# Macro_Mini_keypad.net
KiCad netlist of a schematic drawn in EAGLE
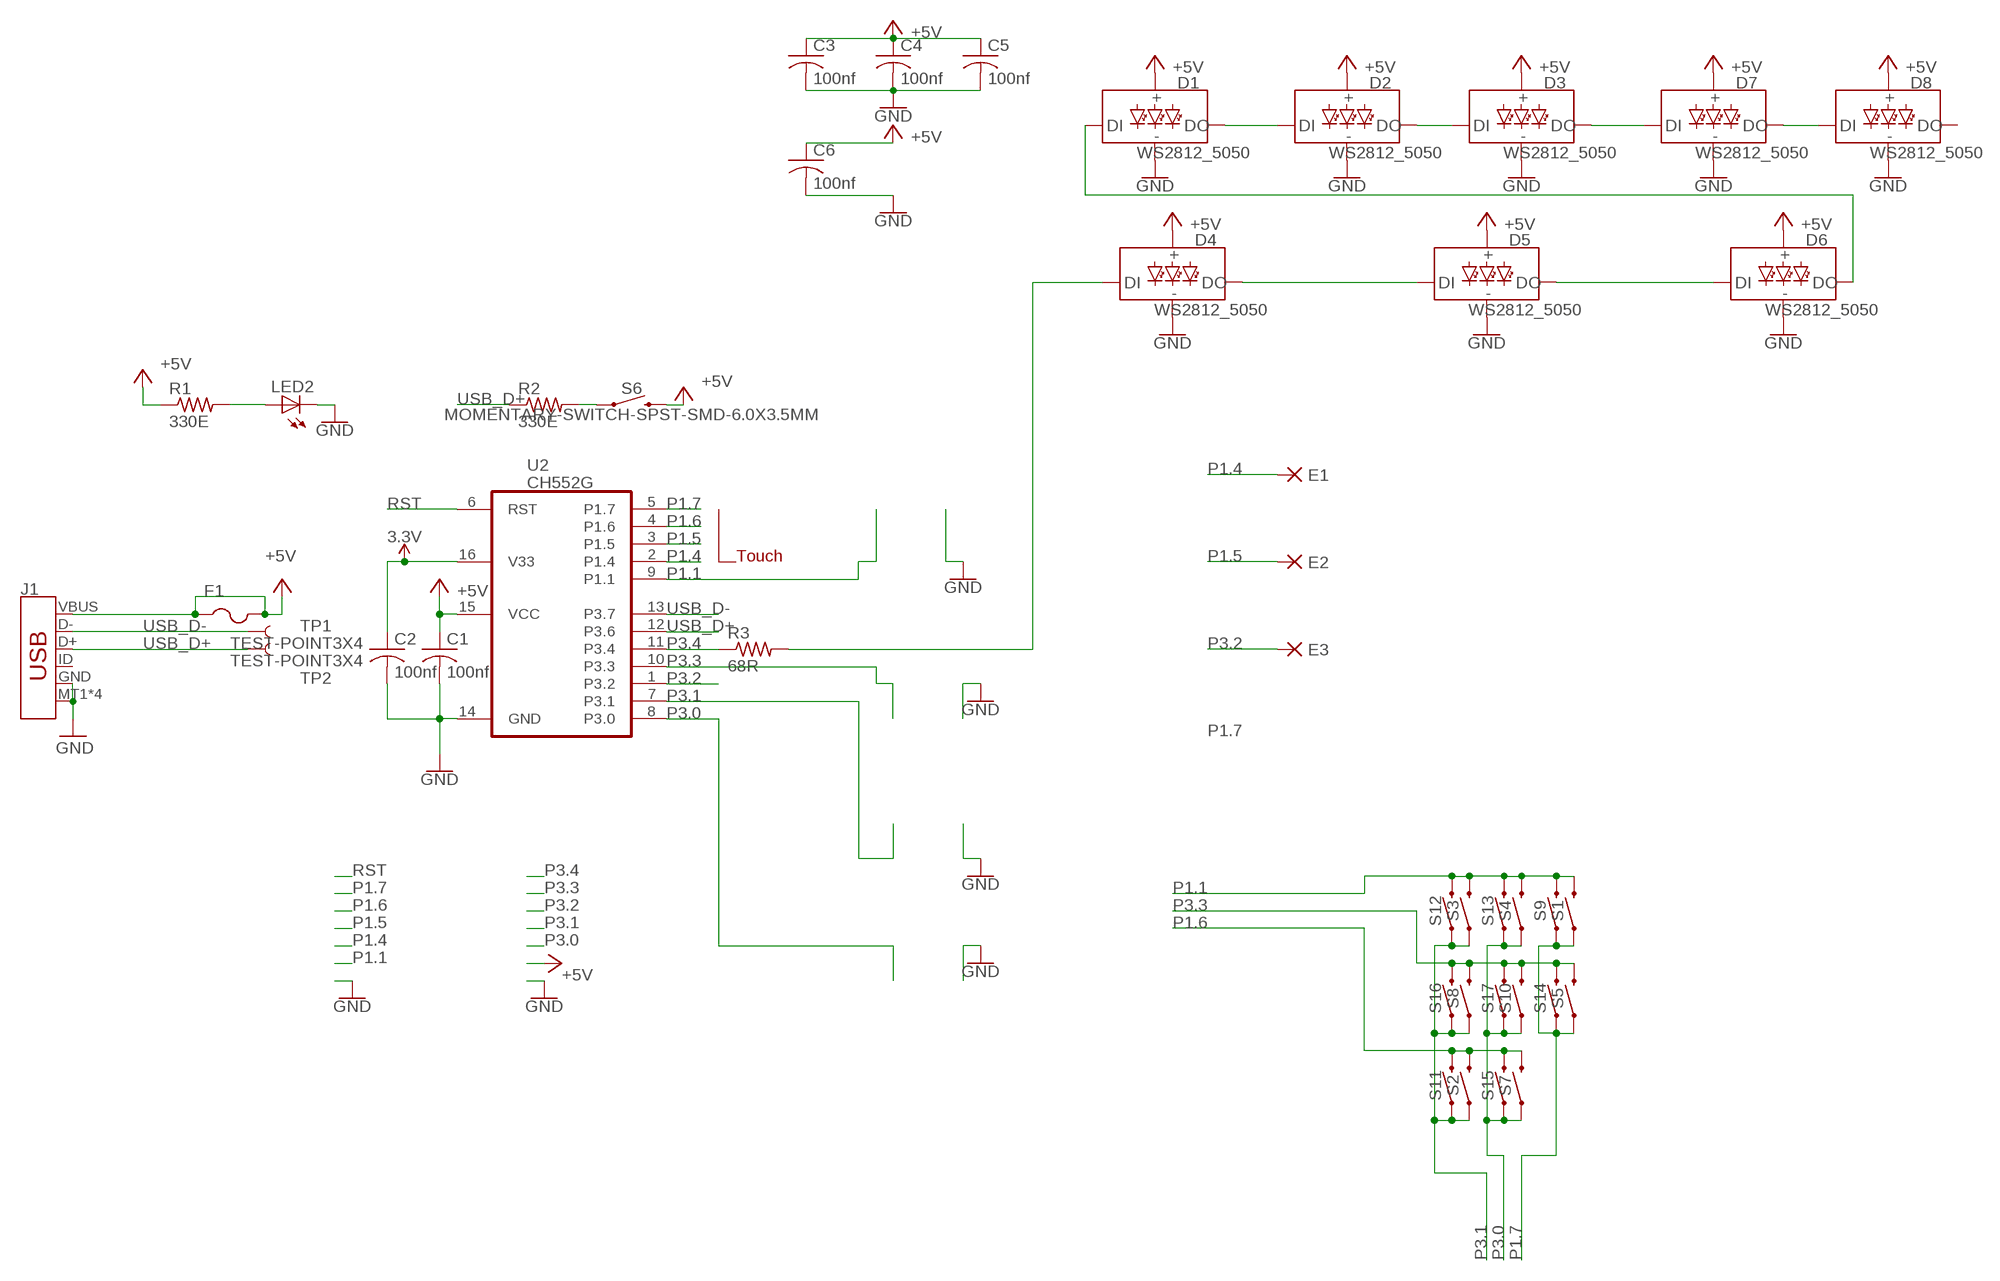
[diagram p0: schematic, sheet 1]

(export (version "E")
  (design (tool "Eeschema 10.0.6"))
  (components
    (comp (ref "C1")
      (value "100nf")
      (footprint "eagle-import:C1206")
      (libsource (lib "eagle-import") (part "C-USC1206"))
    )
    (comp (ref "C2")
      (value "100nf")
      (footprint "eagle-import:C1206")
      (libsource (lib "eagle-import") (part "C-USC1206"))
    )
    (comp (ref "C3")
      (value "100nf")
      (footprint "eagle-import:C1206")
      (libsource (lib "eagle-import") (part "C-USC1206"))
    )
    (comp (ref "C4")
      (value "100nf")
      (footprint "eagle-import:C1206")
      (libsource (lib "eagle-import") (part "C-USC1206"))
    )
    (comp (ref "C5")
      (value "100nf")
      (footprint "eagle-import:C1206")
      (libsource (lib "eagle-import") (part "C-USC1206"))
    )
    (comp (ref "C6")
      (value "100nf")
      (footprint "eagle-import:C1206")
      (libsource (lib "eagle-import") (part "C-USC1206"))
    )
    (comp (ref "D1")
      (value "WS2812_5050")
      (footprint "eagle-import:WS2812-5X5-4PIN")
      (libsource (lib "eagle-import") (part "WS2812_5050"))
    )
    (comp (ref "D2")
      (value "WS2812_5050")
      (footprint "eagle-import:WS2812-5X5-4PIN")
      (libsource (lib "eagle-import") (part "WS2812_5050"))
    )
    (comp (ref "D3")
      (value "WS2812_5050")
      (footprint "eagle-import:WS2812-5X5-4PIN")
      (libsource (lib "eagle-import") (part "WS2812_5050"))
    )
    (comp (ref "D4")
      (value "WS2812_5050")
      (footprint "eagle-import:WS2812-5X5-4PIN")
      (libsource (lib "eagle-import") (part "WS2812_5050"))
    )
    (comp (ref "D5")
      (value "WS2812_5050")
      (footprint "eagle-import:WS2812-5X5-4PIN")
      (libsource (lib "eagle-import") (part "WS2812_5050"))
    )
    (comp (ref "D6")
      (value "WS2812_5050")
      (footprint "eagle-import:WS2812-5X5-4PIN")
      (libsource (lib "eagle-import") (part "WS2812_5050"))
    )
    (comp (ref "D7")
      (value "WS2812_5050")
      (footprint "eagle-import:WS2812-5X5-4PIN")
      (libsource (lib "eagle-import") (part "WS2812_5050"))
    )
    (comp (ref "D8")
      (value "WS2812_5050")
      (footprint "eagle-import:WS2812-5X5-4PIN")
      (libsource (lib "eagle-import") (part "WS2812_5050"))
    )
    (comp (ref "E1")
      (value "DPADS_PAD-0400-S")
      (footprint "eagle-import:DPADS_0400-S")
      (libsource (lib "eagle-import") (part "DPADS_PAD-0400-S"))
    )
    (comp (ref "E2")
      (value "DPADS_PAD-0400-S")
      (footprint "eagle-import:DPADS_0400-S")
      (libsource (lib "eagle-import") (part "DPADS_PAD-0400-S"))
    )
    (comp (ref "E3")
      (value "DPADS_PAD-0400-S")
      (footprint "eagle-import:DPADS_0400-S")
      (libsource (lib "eagle-import") (part "DPADS_PAD-0400-S"))
    )
    (comp (ref "F1")
      (value "PTCFUSE-1206")
      (footprint "eagle-import:R1206")
      (libsource (lib "eagle-import") (part "PTCFUSE-1206"))
    )
    (comp (ref "J1")
      (value "USB_MICRO-B_SMT")
      (footprint "eagle-import:USB-MICROB")
      (libsource (lib "eagle-import") (part "USB_MICRO-B_SMT"))
    )
    (comp (ref "LED2")
      (value "LEDCHIPLED_1206")
      (footprint "eagle-import:CHIPLED_1206")
      (libsource (lib "eagle-import") (part "LEDCHIPLED_1206"))
    )
    (comp (ref "R1")
      (value "330E")
      (footprint "eagle-import:R1206")
      (libsource (lib "eagle-import") (part "R-US_R1206"))
    )
    (comp (ref "R2")
      (value "330E")
      (footprint "eagle-import:R1206")
      (libsource (lib "eagle-import") (part "R-US_R1206"))
    )
    (comp (ref "R3")
      (value "68R")
      (footprint "eagle-import:R1206")
      (libsource (lib "eagle-import") (part "R-US_R1206"))
    )
    (comp (ref "S1")
      (value "MECHANICAL-KEYBOARD_CUSTOM1U")
      (footprint "eagle-import:CHERRY-MX-LED-1U")
      (libsource (lib "eagle-import") (part "MECHANICAL-KEYBOARD_CUSTOM1U"))
    )
    (comp (ref "S2")
      (value "MECHANICAL-KEYBOARD_CUSTOM1U")
      (footprint "eagle-import:CHERRY-MX-LED-1U")
      (libsource (lib "eagle-import") (part "MECHANICAL-KEYBOARD_CUSTOM1U"))
    )
    (comp (ref "S3")
      (value "MECHANICAL-KEYBOARD_CUSTOM1U")
      (footprint "eagle-import:CHERRY-MX-LED-1U")
      (libsource (lib "eagle-import") (part "MECHANICAL-KEYBOARD_CUSTOM1U"))
    )
    (comp (ref "S4")
      (value "MECHANICAL-KEYBOARD_CUSTOM1U")
      (footprint "eagle-import:CHERRY-MX-LED-1U")
      (libsource (lib "eagle-import") (part "MECHANICAL-KEYBOARD_CUSTOM1U"))
    )
    (comp (ref "S5")
      (value "MECHANICAL-KEYBOARD_CUSTOM1U")
      (footprint "eagle-import:CHERRY-MX-LED-1U")
      (libsource (lib "eagle-import") (part "MECHANICAL-KEYBOARD_CUSTOM1U"))
    )
    (comp (ref "S6")
      (value "MOMENTARY-SWITCH-SPST-SMD-6.0X3.5MM")
      (footprint "eagle-import:TACTILE_SWITCH_SMD_6.0X3.5MM")
      (libsource (lib "eagle-import") (part "MOMENTARY-SWITCH-SPST-SMD-6.0X3.5MM"))
    )
    (comp (ref "S7")
      (value "MECHANICAL-KEYBOARD_CUSTOM1U")
      (footprint "eagle-import:CHERRY-MX-LED-1U")
      (libsource (lib "eagle-import") (part "MECHANICAL-KEYBOARD_CUSTOM1U"))
    )
    (comp (ref "S8")
      (value "MECHANICAL-KEYBOARD_CUSTOM1U")
      (footprint "eagle-import:CHERRY-MX-LED-1U")
      (libsource (lib "eagle-import") (part "MECHANICAL-KEYBOARD_CUSTOM1U"))
    )
    (comp (ref "S9")
      (value "MOMENTARY-SWITCH-SPST-PTH-12MM")
      (footprint "eagle-import:TACTILE_SWITCH_PTH_12MM")
      (libsource (lib "eagle-import") (part "SparkFun-Switches_535_MOMENTARY-SWITCH-SPST-PTH-12MM"))
    )
    (comp (ref "S10")
      (value "MECHANICAL-KEYBOARD_CUSTOM1U")
      (footprint "eagle-import:CHERRY-MX-LED-1U")
      (libsource (lib "eagle-import") (part "MECHANICAL-KEYBOARD_CUSTOM1U"))
    )
    (comp (ref "S11")
      (value "MOMENTARY-SWITCH-SPST-PTH-12MM")
      (footprint "eagle-import:TACTILE_SWITCH_PTH_12MM")
      (libsource (lib "eagle-import") (part "SparkFun-Switches_535_MOMENTARY-SWITCH-SPST-PTH-12MM"))
    )
    (comp (ref "S12")
      (value "MOMENTARY-SWITCH-SPST-PTH-12MM")
      (footprint "eagle-import:TACTILE_SWITCH_PTH_12MM")
      (libsource (lib "eagle-import") (part "SparkFun-Switches_535_MOMENTARY-SWITCH-SPST-PTH-12MM"))
    )
    (comp (ref "S13")
      (value "MOMENTARY-SWITCH-SPST-PTH-12MM")
      (footprint "eagle-import:TACTILE_SWITCH_PTH_12MM")
      (libsource (lib "eagle-import") (part "SparkFun-Switches_535_MOMENTARY-SWITCH-SPST-PTH-12MM"))
    )
    (comp (ref "S14")
      (value "MOMENTARY-SWITCH-SPST-PTH-12MM")
      (footprint "eagle-import:TACTILE_SWITCH_PTH_12MM")
      (libsource (lib "eagle-import") (part "SparkFun-Switches_535_MOMENTARY-SWITCH-SPST-PTH-12MM"))
    )
    (comp (ref "S15")
      (value "MOMENTARY-SWITCH-SPST-PTH-12MM")
      (footprint "eagle-import:TACTILE_SWITCH_PTH_12MM")
      (libsource (lib "eagle-import") (part "SparkFun-Switches_535_MOMENTARY-SWITCH-SPST-PTH-12MM"))
    )
    (comp (ref "S16")
      (value "MOMENTARY-SWITCH-SPST-PTH-12MM")
      (footprint "eagle-import:TACTILE_SWITCH_PTH_12MM")
      (libsource (lib "eagle-import") (part "SparkFun-Switches_535_MOMENTARY-SWITCH-SPST-PTH-12MM"))
    )
    (comp (ref "S17")
      (value "MOMENTARY-SWITCH-SPST-PTH-12MM")
      (footprint "eagle-import:TACTILE_SWITCH_PTH_12MM")
      (libsource (lib "eagle-import") (part "SparkFun-Switches_535_MOMENTARY-SWITCH-SPST-PTH-12MM"))
    )
    (comp (ref "TP1")
      (value "TEST-POINT3X4")
      (footprint "eagle-import:PAD.03X.04")
      (libsource (lib "eagle-import") (part "TEST-POINT3X4"))
    )
    (comp (ref "TP2")
      (value "TEST-POINT3X4")
      (footprint "eagle-import:PAD.03X.04")
      (libsource (lib "eagle-import") (part "TEST-POINT3X4"))
    )
    (comp (ref "U2")
      (value "CH552G")
      (footprint "eagle-import:MY_IC_SO16")
      (libsource (lib "eagle-import") (part "MY_IC_CH551G_CH552GSOP-16"))
    )
  )
  (nets
    (net (code "1") (name "+5V") (class "Default")
      (node (ref "C1") (pin "1") (pinfunction "1_1") (pintype "passive"))
      (node (ref "C3") (pin "1") (pinfunction "1_1") (pintype "passive"))
      (node (ref "C4") (pin "1") (pinfunction "1_1") (pintype "passive"))
      (node (ref "C5") (pin "1") (pinfunction "1_1") (pintype "passive"))
      (node (ref "C6") (pin "1") (pinfunction "1_1") (pintype "passive"))
      (node (ref "D1") (pin "VCC") (pinfunction "VCC_VCC") (pintype "bidirectional"))
      (node (ref "D2") (pin "VCC") (pinfunction "VCC_VCC") (pintype "bidirectional"))
      (node (ref "D3") (pin "VCC") (pinfunction "VCC_VCC") (pintype "bidirectional"))
      (node (ref "D4") (pin "VCC") (pinfunction "VCC_VCC") (pintype "bidirectional"))
      (node (ref "D5") (pin "VCC") (pinfunction "VCC_VCC") (pintype "bidirectional"))
      (node (ref "D6") (pin "VCC") (pinfunction "VCC_VCC") (pintype "bidirectional"))
      (node (ref "D7") (pin "VCC") (pinfunction "VCC_VCC") (pintype "bidirectional"))
      (node (ref "D8") (pin "VCC") (pinfunction "VCC_VCC") (pintype "bidirectional"))
      (node (ref "F1") (pin "1") (pinfunction "1_1") (pintype "passive"))
      (node (ref "F1") (pin "2") (pinfunction "2_2") (pintype "passive"))
      (node (ref "J1") (pin "VBUS") (pinfunction "VBUS_VBUS") (pintype "power_in"))
      (node (ref "R1") (pin "1") (pinfunction "1_1") (pintype "passive"))
      (node (ref "S6") (pin "2") (pinfunction "2_2") (pintype "passive"))
      (node (ref "U2") (pin "15") (pinfunction "VCC_15") (pintype "power_in"))
    )
    (net (code "2") (name "/P1.1") (class "Default")
      (node (ref "S1") (pin "S2") (pinfunction "2_S2") (pintype "passive"))
      (node (ref "S12") (pin "3") (pinfunction "2_3") (pintype "passive"))
      (node (ref "S13") (pin "3") (pinfunction "2_3") (pintype "passive"))
      (node (ref "S3") (pin "S2") (pinfunction "2_S2") (pintype "passive"))
      (node (ref "S4") (pin "S2") (pinfunction "2_S2") (pintype "passive"))
      (node (ref "S9") (pin "3") (pinfunction "2_3") (pintype "passive"))
      (node (ref "U2") (pin "9") (pinfunction "P1.1_9") (pintype "bidirectional"))
    )
    (net (code "3") (name "/P1.4") (class "Default")
      (node (ref "E1") (pin "PAD") (pinfunction "P_PAD") (pintype "passive"))
      (node (ref "U2") (pin "2") (pinfunction "P1.4_2") (pintype "bidirectional"))
    )
    (net (code "4") (name "/P1.5") (class "Default")
      (node (ref "E2") (pin "PAD") (pinfunction "P_PAD") (pintype "passive"))
      (node (ref "U2") (pin "3") (pinfunction "P1.5_3") (pintype "bidirectional"))
    )
    (net (code "5") (name "/P1.6") (class "Default")
      (node (ref "S11") (pin "3") (pinfunction "2_3") (pintype "passive"))
      (node (ref "S15") (pin "3") (pinfunction "2_3") (pintype "passive"))
      (node (ref "S2") (pin "S2") (pinfunction "2_S2") (pintype "passive"))
      (node (ref "S7") (pin "S2") (pinfunction "2_S2") (pintype "passive"))
      (node (ref "U2") (pin "4") (pinfunction "P1.6_4") (pintype "bidirectional"))
    )
    (net (code "6") (name "/P1.7") (class "Default")
      (node (ref "S1") (pin "S1") (pinfunction "1_S1") (pintype "passive"))
      (node (ref "S14") (pin "1") (pinfunction "1_1") (pintype "passive"))
      (node (ref "S5") (pin "S1") (pinfunction "1_S1") (pintype "passive"))
      (node (ref "S9") (pin "1") (pinfunction "1_1") (pintype "passive"))
      (node (ref "U2") (pin "5") (pinfunction "P1.7_5") (pintype "bidirectional"))
    )
    (net (code "7") (name "/P3.0") (class "Default")
      (node (ref "S10") (pin "S1") (pinfunction "1_S1") (pintype "passive"))
      (node (ref "S13") (pin "1") (pinfunction "1_1") (pintype "passive"))
      (node (ref "S15") (pin "1") (pinfunction "1_1") (pintype "passive"))
      (node (ref "S17") (pin "1") (pinfunction "1_1") (pintype "passive"))
      (node (ref "S4") (pin "S1") (pinfunction "1_S1") (pintype "passive"))
      (node (ref "S7") (pin "S1") (pinfunction "1_S1") (pintype "passive"))
      (node (ref "U2") (pin "8") (pinfunction "P3.0_8") (pintype "bidirectional"))
    )
    (net (code "8") (name "/P3.1") (class "Default")
      (node (ref "S11") (pin "1") (pinfunction "1_1") (pintype "passive"))
      (node (ref "S12") (pin "1") (pinfunction "1_1") (pintype "passive"))
      (node (ref "S16") (pin "1") (pinfunction "1_1") (pintype "passive"))
      (node (ref "S2") (pin "S1") (pinfunction "1_S1") (pintype "passive"))
      (node (ref "S3") (pin "S1") (pinfunction "1_S1") (pintype "passive"))
      (node (ref "S8") (pin "S1") (pinfunction "1_S1") (pintype "passive"))
      (node (ref "U2") (pin "7") (pinfunction "P3.1_7") (pintype "bidirectional"))
    )
    (net (code "9") (name "/P3.2") (class "Default")
      (node (ref "E3") (pin "PAD") (pinfunction "P_PAD") (pintype "passive"))
      (node (ref "U2") (pin "1") (pinfunction "P3.2_1") (pintype "bidirectional"))
    )
    (net (code "10") (name "/P3.3") (class "Default")
      (node (ref "S10") (pin "S2") (pinfunction "2_S2") (pintype "passive"))
      (node (ref "S14") (pin "3") (pinfunction "2_3") (pintype "passive"))
      (node (ref "S16") (pin "3") (pinfunction "2_3") (pintype "passive"))
      (node (ref "S17") (pin "3") (pinfunction "2_3") (pintype "passive"))
      (node (ref "S5") (pin "S2") (pinfunction "2_S2") (pintype "passive"))
      (node (ref "S8") (pin "S2") (pinfunction "2_S2") (pintype "passive"))
      (node (ref "U2") (pin "10") (pinfunction "P3.3_10") (pintype "bidirectional"))
    )
    (net (code "11") (name "/P3.4") (class "Default")
      (node (ref "R3") (pin "1") (pinfunction "1_1") (pintype "passive"))
      (node (ref "U2") (pin "11") (pinfunction "P3.4_11") (pintype "bidirectional"))
    )
    (net (code "12") (name "/RST") (class "Default")
      (node (ref "U2") (pin "6") (pinfunction "RST_6") (pintype "input"))
    )
    (net (code "13") (name "/USB_D+") (class "Default")
      (node (ref "J1") (pin "D+") (pinfunction "D+_D+") (pintype "bidirectional"))
      (node (ref "R2") (pin "1") (pinfunction "1_1") (pintype "passive"))
      (node (ref "TP2") (pin "P$1") (pinfunction "1_P$1") (pintype "bidirectional"))
      (node (ref "U2") (pin "12") (pinfunction "P3.6_12") (pintype "bidirectional"))
    )
    (net (code "14") (name "/USB_D-") (class "Default")
      (node (ref "J1") (pin "D-") (pinfunction "D-_D-") (pintype "bidirectional"))
      (node (ref "TP1") (pin "P$1") (pinfunction "1_P$1") (pintype "bidirectional"))
      (node (ref "U2") (pin "13") (pinfunction "P3.7_13") (pintype "bidirectional"))
    )
    (net (code "15") (name "3.3V") (class "Default")
      (node (ref "C2") (pin "1") (pinfunction "1_1") (pintype "passive"))
      (node (ref "U2") (pin "16") (pinfunction "V33_16") (pintype "power_in"))
    )
    (net (code "16") (name "GND") (class "Default")
      (node (ref "C1") (pin "2") (pinfunction "2_2") (pintype "passive"))
      (node (ref "C2") (pin "2") (pinfunction "2_2") (pintype "passive"))
      (node (ref "C3") (pin "2") (pinfunction "2_2") (pintype "passive"))
      (node (ref "C4") (pin "2") (pinfunction "2_2") (pintype "passive"))
      (node (ref "C5") (pin "2") (pinfunction "2_2") (pintype "passive"))
      (node (ref "C6") (pin "2") (pinfunction "2_2") (pintype "passive"))
      (node (ref "D1") (pin "GND") (pinfunction "GND_GND") (pintype "bidirectional"))
      (node (ref "D2") (pin "GND") (pinfunction "GND_GND") (pintype "bidirectional"))
      (node (ref "D3") (pin "GND") (pinfunction "GND_GND") (pintype "bidirectional"))
      (node (ref "D4") (pin "GND") (pinfunction "GND_GND") (pintype "bidirectional"))
      (node (ref "D5") (pin "GND") (pinfunction "GND_GND") (pintype "bidirectional"))
      (node (ref "D6") (pin "GND") (pinfunction "GND_GND") (pintype "bidirectional"))
      (node (ref "D7") (pin "GND") (pinfunction "GND_GND") (pintype "bidirectional"))
      (node (ref "D8") (pin "GND") (pinfunction "GND_GND") (pintype "bidirectional"))
      (node (ref "J1") (pin "GND") (pinfunction "GND_GND") (pintype "power_in"))
      (node (ref "J1") (pin "MT1") (pinfunction "SHIELD_MT1") (pintype "bidirectional"))
      (node (ref "J1") (pin "MT2") (pinfunction "SHIELD_MT2") (pintype "bidirectional"))
      (node (ref "J1") (pin "P$1") (pinfunction "SHIELD_P$1") (pintype "bidirectional"))
      (node (ref "J1") (pin "P$2") (pinfunction "SHIELD_P$2") (pintype "bidirectional"))
      (node (ref "LED2") (pin "C") (pinfunction "C_C") (pintype "passive"))
      (node (ref "U2") (pin "14") (pinfunction "GND_14") (pintype "power_in"))
    )
    (net (code "17") (name "Net-(D1-PadDI)") (class "Default")
      (node (ref "D1") (pin "DI") (pinfunction "DI_DI") (pintype "bidirectional"))
      (node (ref "D6") (pin "DO") (pinfunction "DO_DO") (pintype "bidirectional"))
    )
    (net (code "18") (name "Net-(D1-PadDO)") (class "Default")
      (node (ref "D1") (pin "DO") (pinfunction "DO_DO") (pintype "bidirectional"))
      (node (ref "D2") (pin "DI") (pinfunction "DI_DI") (pintype "bidirectional"))
    )
    (net (code "19") (name "Net-(D2-PadDO)") (class "Default")
      (node (ref "D2") (pin "DO") (pinfunction "DO_DO") (pintype "bidirectional"))
      (node (ref "D3") (pin "DI") (pinfunction "DI_DI") (pintype "bidirectional"))
    )
    (net (code "20") (name "Net-(D3-PadDO)") (class "Default")
      (node (ref "D3") (pin "DO") (pinfunction "DO_DO") (pintype "bidirectional"))
      (node (ref "D7") (pin "DI") (pinfunction "DI_DI") (pintype "bidirectional"))
    )
    (net (code "21") (name "Net-(D4-PadDI)") (class "Default")
      (node (ref "D4") (pin "DI") (pinfunction "DI_DI") (pintype "bidirectional"))
      (node (ref "R3") (pin "2") (pinfunction "2_2") (pintype "passive"))
    )
    (net (code "22") (name "Net-(D4-PadDO)") (class "Default")
      (node (ref "D4") (pin "DO") (pinfunction "DO_DO") (pintype "bidirectional"))
      (node (ref "D5") (pin "DI") (pinfunction "DI_DI") (pintype "bidirectional"))
    )
    (net (code "23") (name "Net-(D5-PadDO)") (class "Default")
      (node (ref "D5") (pin "DO") (pinfunction "DO_DO") (pintype "bidirectional"))
      (node (ref "D6") (pin "DI") (pinfunction "DI_DI") (pintype "bidirectional"))
    )
    (net (code "24") (name "Net-(D7-PadDO)") (class "Default")
      (node (ref "D7") (pin "DO") (pinfunction "DO_DO") (pintype "bidirectional"))
      (node (ref "D8") (pin "DI") (pinfunction "DI_DI") (pintype "bidirectional"))
    )
    (net (code "25") (name "Net-(LED2-PadA)") (class "Default")
      (node (ref "LED2") (pin "A") (pinfunction "A_A") (pintype "passive"))
      (node (ref "R1") (pin "2") (pinfunction "2_2") (pintype "passive"))
    )
    (net (code "26") (name "Net-(R2-Pad2)") (class "Default")
      (node (ref "R2") (pin "2") (pinfunction "2_2") (pintype "passive"))
      (node (ref "S6") (pin "1") (pinfunction "1_1") (pintype "passive"))
    )
    (net (code "27") (name "unconnected-(D8-PadDO)") (class "Default")
      (node (ref "D8") (pin "DO") (pinfunction "DO_DO") (pintype "bidirectional"))
    )
    (net (code "28") (name "unconnected-(J1-PadID)") (class "Default")
      (node (ref "J1") (pin "ID") (pinfunction "ID_ID") (pintype "bidirectional"))
    )
  )
)
